# efm8sb1-dev-board.net
KiCad netlist of a schematic drawn in Altium Designer
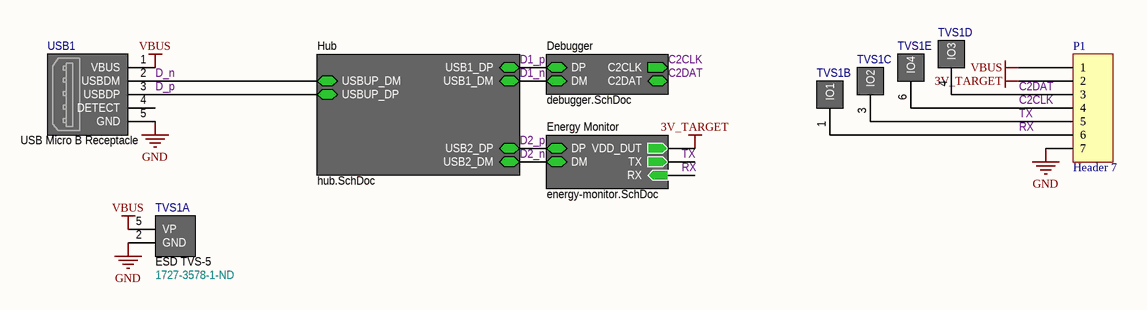
[diagram p0: efm8sb1-dev-board.SchDoc]

(export (version "E")
  (design (tool "Eeschema 10.0.6"))
  (components
    (comp (ref "P1")
      (value "Header 7")
      (footprint "HDR1X7-PINS")
      (description "Header, 7-Pin")
      (fields (field (name "PUBLISHER") "Altium Limited"))
      (libsource (lib "Miscellaneous Connectors") (part "Header 7"))
    )
    (comp (ref "TVS1")
      (value "ESD TVS-5")
      (footprint "SOT26A-6N")
      (description "5-channel ESD protection device for USB")
      (fields (field (name "SUPPLIER PART NUMBER 1") "1727-3578-1-ND"))
      (libsource (lib "") (part "ESD TVS-5_1"))
    )
    (comp (ref "USB1")
      (value "USB Micro B Receptacle")
      (footprint "10118193-0001LF")
      (libsource (lib "Miscellaneous Connectors") (part "USB Micro B Receptacle"))
    )
  )
  (nets
    (net (code "1") (name "/C2CLK") (class "Default")
      (node (ref "P1") (pin "4") (pinfunction "4_4") (pintype "passive"))
      (node (ref "TVS1") (pin "6") (pinfunction "IO4_6") (pintype "passive"))
    )
    (net (code "2") (name "/C2DAT") (class "Default")
      (node (ref "P1") (pin "3") (pinfunction "3_3") (pintype "passive"))
      (node (ref "TVS1") (pin "4") (pinfunction "IO3_4") (pintype "passive"))
    )
    (net (code "7") (name "/D_n") (class "Default")
      (node (ref "USB1") (pin "2") (pinfunction "USBDM_2") (pintype "power_in"))
    )
    (net (code "8") (name "/D_p") (class "Default")
      (node (ref "USB1") (pin "3") (pinfunction "USBDP_3") (pintype "power_in"))
    )
    (net (code "9") (name "/RX") (class "Default")
      (node (ref "P1") (pin "6") (pinfunction "6_6") (pintype "passive"))
      (node (ref "TVS1") (pin "1") (pinfunction "IO1_1") (pintype "passive"))
    )
    (net (code "10") (name "/TX") (class "Default")
      (node (ref "P1") (pin "5") (pinfunction "5_5") (pintype "passive"))
      (node (ref "TVS1") (pin "3") (pinfunction "IO2_3") (pintype "passive"))
    )
    (net (code "11") (name "3V_TARGET") (class "Default")
      (node (ref "P1") (pin "2") (pinfunction "2_2") (pintype "passive"))
    )
    (net (code "12") (name "GND") (class "Default")
      (node (ref "P1") (pin "7") (pinfunction "7_7") (pintype "passive"))
      (node (ref "TVS1") (pin "2") (pinfunction "GND_2") (pintype "power_in"))
      (node (ref "USB1") (pin "5") (pinfunction "GND_5") (pintype "power_in"))
    )
    (net (code "13") (name "VBUS") (class "Default")
      (node (ref "P1") (pin "1") (pinfunction "1_1") (pintype "passive"))
      (node (ref "TVS1") (pin "5") (pinfunction "VP_5") (pintype "power_in"))
      (node (ref "USB1") (pin "1") (pinfunction "VBUS_1") (pintype "power_in"))
    )
    (net (code "14") (name "unconnected-(USB1-DETECT-Pad4)") (class "Default")
      (node (ref "USB1") (pin "4") (pinfunction "DETECT_4") (pintype "power_in"))
    )
  )
)
